# Sheet2.net
KiCad netlist of a schematic drawn in Altium Designer
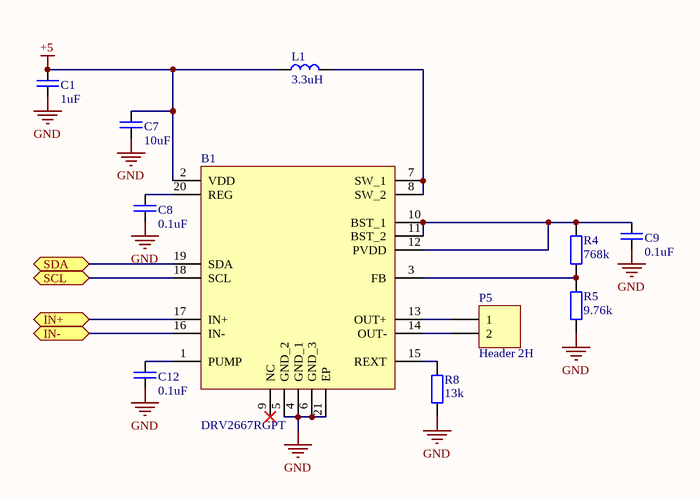
[diagram p0: Sheet2.SchDoc]

(export (version "E")
  (design (tool "Eeschema 10.0.6"))
  (components
    (comp (ref "B1")
      (value "DRV2667RGPT")
      (footprint "QFN50P400X400X100-21N-D")
      (description "Motor / Motion / Ignition Controllers & Drivers Piezo Haptic Dvr w/ Boost Digital FE")
      (fields (field (name "MOUSER PART NUMBER") "595-DRV2667RGPT"))
      (libsource (lib "DRV2667RGPT") (part "DRV2667RGPT"))
    )
    (comp (ref "C1")
      (value "1uF")
      (footprint "C2012_0805I_M")
      (description "Capacitor")
      (libsource (lib "General") (part "C"))
    )
    (comp (ref "C7")
      (value "10uF")
      (footprint "C2012_0805I_M")
      (description "Capacitor")
      (libsource (lib "General") (part "C"))
    )
    (comp (ref "C8")
      (value "0.1uF")
      (footprint "R1005_0402i_M")
      (description "Capacitor")
      (libsource (lib "General") (part "C"))
    )
    (comp (ref "C9")
      (value "0.1uF")
      (footprint "C3216_1206I_L")
      (description "Capacitor")
      (libsource (lib "General") (part "C"))
    )
    (comp (ref "C12")
      (value "0.1uF")
      (footprint "R1005_0402i_M")
      (description "Capacitor")
      (libsource (lib "General") (part "C"))
    )
    (comp (ref "L1")
      (value "3.3uH")
      (footprint "INDUCTOR")
      (description "L")
      (libsource (lib "PiVO_shield") (part "L"))
    )
    (comp (ref "P5")
      (value "Header 2H")
      (footprint "HDR1X2H")
      (description "Header, 2-Pin, Right Angle")
      (fields (field (name "PUBLISHER") "Altium Limited"))
      (libsource (lib "Miscellaneous Connectors") (part "Header 2H"))
    )
    (comp (ref "R4")
      (value "768k")
      (footprint "R1005_0402i_M")
      (description "R")
      (libsource (lib "General") (part "R"))
    )
    (comp (ref "R5")
      (value "9.76k")
      (footprint "R1005_0402i_M")
      (description "R")
      (libsource (lib "General") (part "R"))
    )
    (comp (ref "R8")
      (value "13k")
      (footprint "R1005_0402i_M")
      (description "R")
      (libsource (lib "General") (part "R"))
    )
  )
  (nets
    (net (code "1") (name "+5") (class "Default")
      (node (ref "B1") (pin "2") (pinfunction "VDD_2") (pintype "passive"))
      (node (ref "C1") (pin "1") (pinfunction "1_1") (pintype "passive"))
      (node (ref "C7") (pin "1") (pinfunction "1_1") (pintype "passive"))
      (node (ref "L1") (pin "1") (pintype "passive"))
    )
    (net (code "2") (name "/IN+") (class "Default")
      (node (ref "B1") (pin "17") (pinfunction "IN+_17") (pintype "passive"))
    )
    (net (code "3") (name "/IN-") (class "Default")
      (node (ref "B1") (pin "16") (pinfunction "IN-_16") (pintype "passive"))
    )
    (net (code "4") (name "/SCL") (class "Default")
      (node (ref "B1") (pin "18") (pinfunction "SCL_18") (pintype "passive"))
    )
    (net (code "5") (name "/SDA") (class "Default")
      (node (ref "B1") (pin "19") (pinfunction "SDA_19") (pintype "passive"))
    )
    (net (code "6") (name "GND") (class "Default")
      (node (ref "B1") (pin "21") (pinfunction "EP_21") (pintype "passive"))
      (node (ref "B1") (pin "4") (pinfunction "GND_1_4") (pintype "passive"))
      (node (ref "B1") (pin "5") (pinfunction "GND_2_5") (pintype "passive"))
      (node (ref "B1") (pin "6") (pinfunction "GND_3_6") (pintype "passive"))
      (node (ref "C1") (pin "2") (pinfunction "2_2") (pintype "passive"))
      (node (ref "C12") (pin "2") (pinfunction "2_2") (pintype "passive"))
      (node (ref "C7") (pin "2") (pinfunction "2_2") (pintype "passive"))
      (node (ref "C8") (pin "2") (pinfunction "2_2") (pintype "passive"))
      (node (ref "C9") (pin "2") (pinfunction "2_2") (pintype "passive"))
      (node (ref "R5") (pin "2") (pintype "passive"))
      (node (ref "R8") (pin "2") (pintype "passive"))
    )
    (net (code "7") (name "Net-(B1-BST_1)") (class "Default")
      (node (ref "B1") (pin "10") (pinfunction "BST_1_10") (pintype "passive"))
      (node (ref "B1") (pin "11") (pinfunction "BST_2_11") (pintype "passive"))
      (node (ref "B1") (pin "12") (pinfunction "PVDD_12") (pintype "passive"))
      (node (ref "C9") (pin "1") (pinfunction "1_1") (pintype "passive"))
      (node (ref "R4") (pin "1") (pintype "passive"))
    )
    (net (code "8") (name "Net-(B1-FB)") (class "Default")
      (node (ref "B1") (pin "3") (pinfunction "FB_3") (pintype "passive"))
      (node (ref "R4") (pin "2") (pintype "passive"))
      (node (ref "R5") (pin "1") (pintype "passive"))
    )
    (net (code "9") (name "Net-(B1-OUT+)") (class "Default")
      (node (ref "B1") (pin "13") (pinfunction "OUT+_13") (pintype "passive"))
      (node (ref "P5") (pin "1") (pinfunction "1_1") (pintype "passive"))
    )
    (net (code "10") (name "Net-(B1-OUT-)") (class "Default")
      (node (ref "B1") (pin "14") (pinfunction "OUT-_14") (pintype "passive"))
      (node (ref "P5") (pin "2") (pinfunction "2_2") (pintype "passive"))
    )
    (net (code "11") (name "Net-(B1-PUMP)") (class "Default")
      (node (ref "B1") (pin "1") (pinfunction "PUMP_1") (pintype "passive"))
      (node (ref "C12") (pin "1") (pinfunction "1_1") (pintype "passive"))
    )
    (net (code "12") (name "Net-(B1-REG)") (class "Default")
      (node (ref "B1") (pin "20") (pinfunction "REG_20") (pintype "passive"))
      (node (ref "C8") (pin "1") (pinfunction "1_1") (pintype "passive"))
    )
    (net (code "13") (name "Net-(B1-REXT)") (class "Default")
      (node (ref "B1") (pin "15") (pinfunction "REXT_15") (pintype "passive"))
      (node (ref "R8") (pin "1") (pintype "passive"))
    )
    (net (code "14") (name "Net-(B1-SW_1)") (class "Default")
      (node (ref "B1") (pin "7") (pinfunction "SW_1_7") (pintype "passive"))
      (node (ref "B1") (pin "8") (pinfunction "SW_2_8") (pintype "passive"))
      (node (ref "L1") (pin "2") (pintype "passive"))
    )
    (net (code "15") (name "unconnected-(B1-NC-Pad9)") (class "Default")
      (node (ref "B1") (pin "9") (pinfunction "NC_9") (pintype "passive+no_connect"))
    )
  )
)
